# Adafruit_NeoKey_FeatherWing.net
KiCad netlist of a schematic drawn in EAGLE
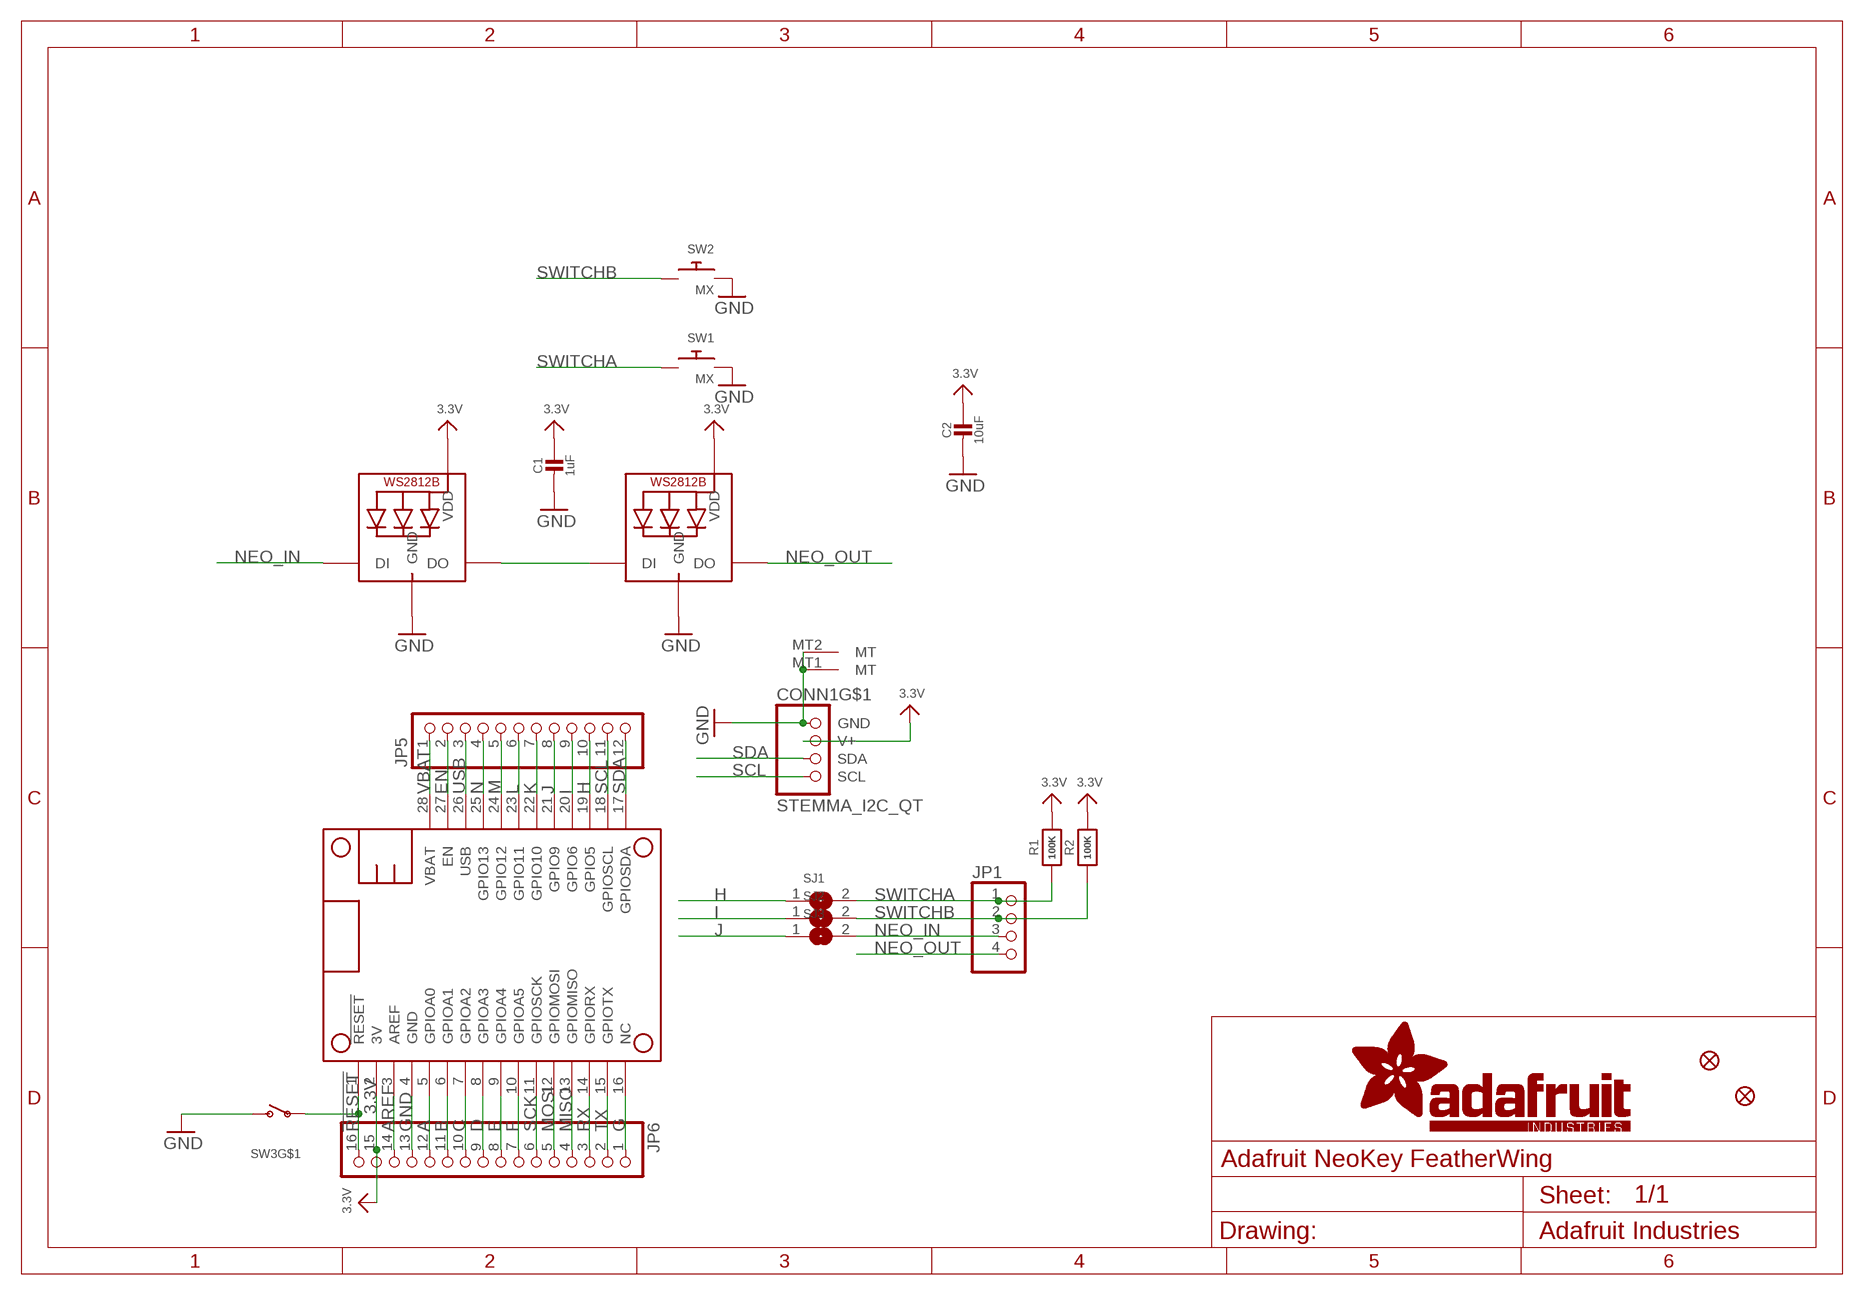
[diagram p0: schematic, sheet 1]

(export (version "E")
  (design (tool "Eeschema 10.0.6"))
  (components
    (comp (ref "C1")
      (value "1uF")
      (footprint "eagle-import:0603-NO")
      (libsource (lib "eagle-import") (part "CAP_CERAMIC0603_NO"))
    )
    (comp (ref "C2")
      (value "10uF")
      (footprint "eagle-import:0805-NO")
      (libsource (lib "eagle-import") (part "CAP_CERAMIC0805-NOOUTLINE"))
    )
    (comp (ref "CONN1")
      (value "STEMMA_I2C_QT")
      (footprint "eagle-import:JST_SH4")
      (libsource (lib "eagle-import") (part "STEMMA_I2C_QT"))
    )
    (comp (ref "FID1")
      (value "FIDUCIAL_1MM")
      (footprint "eagle-import:FIDUCIAL_1MM")
      (libsource (lib "eagle-import") (part "FIDUCIAL_1MM"))
    )
    (comp (ref "FID2")
      (value "FIDUCIAL_1MM")
      (footprint "eagle-import:FIDUCIAL_1MM")
      (libsource (lib "eagle-import") (part "FIDUCIAL_1MM"))
    )
    (comp (ref "JP1")
      (value "HEADER-1X4ROUND")
      (footprint "eagle-import:1X04_ROUND")
      (libsource (lib "eagle-import") (part "HEADER-1X4ROUND"))
    )
    (comp (ref "JP5")
      (value "HEADER-1X12")
      (footprint "eagle-import:1X12_ROUND")
      (libsource (lib "eagle-import") (part "HEADER-1X12"))
    )
    (comp (ref "JP6")
      (value "HEADER-1X16ROUND")
      (footprint "eagle-import:1X16_ROUND")
      (libsource (lib "eagle-import") (part "HEADER-1X16ROUND"))
    )
    (comp (ref "LED1")
      (value "WS2812B_SK6812E")
      (footprint "eagle-import:NEO3535_REVERSE")
      (libsource (lib "eagle-import") (part "WS2812B_SK6812E"))
    )
    (comp (ref "LED2")
      (value "WS2812B_SK6812E")
      (footprint "eagle-import:NEO3535_REVERSE")
      (libsource (lib "eagle-import") (part "WS2812B_SK6812E"))
    )
    (comp (ref "MS1")
      (value "FEATHERWING_NODIM")
      (footprint "eagle-import:FEATHERWING_NODIM")
      (libsource (lib "eagle-import") (part "FEATHERWING_NODIM"))
    )
    (comp (ref "R1")
      (value "100K")
      (footprint "eagle-import:0603-NO")
      (libsource (lib "eagle-import") (part "RESISTOR_0603_NOOUT"))
    )
    (comp (ref "R2")
      (value "100K")
      (footprint "eagle-import:0603-NO")
      (libsource (lib "eagle-import") (part "RESISTOR_0603_NOOUT"))
    )
    (comp (ref "SJ1")
      (value "SOLDERJUMPERCLOSED")
      (footprint "eagle-import:SOLDERJUMPER_CLOSEDWIRE")
      (libsource (lib "eagle-import") (part "SOLDERJUMPERCLOSED"))
    )
    (comp (ref "SJ2")
      (value "SOLDERJUMPERCLOSED")
      (footprint "eagle-import:SOLDERJUMPER_CLOSEDWIRE")
      (libsource (lib "eagle-import") (part "SOLDERJUMPERCLOSED"))
    )
    (comp (ref "SJ3")
      (value "SOLDERJUMPERCLOSED")
      (footprint "eagle-import:SOLDERJUMPER_CLOSEDWIRE")
      (libsource (lib "eagle-import") (part "SOLDERJUMPERCLOSED"))
    )
    (comp (ref "SW1")
      (value "MX")
      (footprint "eagle-import:KAILH_SOCKET")
      (libsource (lib "eagle-import") (part "SWITCH_PUSHBUTTON_KAILH_SOCKET"))
    )
    (comp (ref "SW2")
      (value "MX")
      (footprint "eagle-import:KAILH_SOCKET")
      (libsource (lib "eagle-import") (part "SWITCH_PUSHBUTTON_KAILH_SOCKET"))
    )
    (comp (ref "SW3")
      (value "SWITCH_SPST_TACT_RA")
      (footprint "eagle-import:SPST_TACTILE_RA")
      (libsource (lib "eagle-import") (part "SWITCH_SPST_TACT_RA"))
    )
  )
  (nets
    (net (code "1") (name "/A") (class "Default")
      (node (ref "JP6") (pin "12") (pinfunction "12_12") (pintype "passive"))
      (node (ref "MS1") (pin "5") (pinfunction "GPIOA0_5") (pintype "bidirectional"))
    )
    (net (code "2") (name "/AREF") (class "Default")
      (node (ref "JP6") (pin "14") (pinfunction "14_14") (pintype "passive"))
      (node (ref "MS1") (pin "3") (pinfunction "AREF_3") (pintype "passive"))
    )
    (net (code "3") (name "/B") (class "Default")
      (node (ref "JP6") (pin "11") (pinfunction "11_11") (pintype "passive"))
      (node (ref "MS1") (pin "6") (pinfunction "GPIOA1_6") (pintype "bidirectional"))
    )
    (net (code "4") (name "/C") (class "Default")
      (node (ref "JP6") (pin "10") (pinfunction "10_10") (pintype "passive"))
      (node (ref "MS1") (pin "7") (pinfunction "GPIOA2_7") (pintype "bidirectional"))
    )
    (net (code "5") (name "/D") (class "Default")
      (node (ref "JP6") (pin "9") (pinfunction "9_9") (pintype "passive"))
      (node (ref "MS1") (pin "8") (pinfunction "GPIOA3_8") (pintype "bidirectional"))
    )
    (net (code "6") (name "/E") (class "Default")
      (node (ref "JP6") (pin "8") (pinfunction "8_8") (pintype "passive"))
      (node (ref "MS1") (pin "9") (pinfunction "GPIOA4_9") (pintype "bidirectional"))
    )
    (net (code "7") (name "/EN") (class "Default")
      (node (ref "JP5") (pin "2") (pinfunction "2_2") (pintype "passive"))
      (node (ref "MS1") (pin "27") (pinfunction "EN_27") (pintype "passive"))
    )
    (net (code "8") (name "/F") (class "Default")
      (node (ref "JP6") (pin "7") (pinfunction "7_7") (pintype "passive"))
      (node (ref "MS1") (pin "10") (pinfunction "GPIOA5_10") (pintype "bidirectional"))
    )
    (net (code "9") (name "/G") (class "Default")
      (node (ref "JP6") (pin "1") (pinfunction "1_1") (pintype "passive"))
      (node (ref "MS1") (pin "16") (pinfunction "NC_16") (pintype "passive"))
    )
    (net (code "10") (name "/H") (class "Default")
      (node (ref "JP5") (pin "10") (pinfunction "10_10") (pintype "passive"))
      (node (ref "MS1") (pin "19") (pinfunction "GPIO5_19") (pintype "bidirectional"))
      (node (ref "SJ1") (pin "1") (pinfunction "1_1") (pintype "passive"))
    )
    (net (code "11") (name "/I") (class "Default")
      (node (ref "JP5") (pin "9") (pinfunction "9_9") (pintype "passive"))
      (node (ref "MS1") (pin "20") (pinfunction "GPIO6_20") (pintype "bidirectional"))
      (node (ref "SJ2") (pin "1") (pinfunction "1_1") (pintype "passive"))
    )
    (net (code "12") (name "/J") (class "Default")
      (node (ref "JP5") (pin "8") (pinfunction "8_8") (pintype "passive"))
      (node (ref "MS1") (pin "21") (pinfunction "GPIO9_21") (pintype "bidirectional"))
      (node (ref "SJ3") (pin "1") (pinfunction "1_1") (pintype "passive"))
    )
    (net (code "13") (name "/K") (class "Default")
      (node (ref "JP5") (pin "7") (pinfunction "7_7") (pintype "passive"))
      (node (ref "MS1") (pin "22") (pinfunction "GPIO10_22") (pintype "bidirectional"))
    )
    (net (code "14") (name "/L") (class "Default")
      (node (ref "JP5") (pin "6") (pinfunction "6_6") (pintype "passive"))
      (node (ref "MS1") (pin "23") (pinfunction "GPIO11_23") (pintype "bidirectional"))
    )
    (net (code "15") (name "/M") (class "Default")
      (node (ref "JP5") (pin "5") (pinfunction "5_5") (pintype "passive"))
      (node (ref "MS1") (pin "24") (pinfunction "GPIO12_24") (pintype "bidirectional"))
    )
    (net (code "16") (name "/MISO") (class "Default")
      (node (ref "JP6") (pin "4") (pinfunction "4_4") (pintype "passive"))
      (node (ref "MS1") (pin "13") (pinfunction "GPIOMISO_13") (pintype "bidirectional"))
    )
    (net (code "17") (name "/MOSI") (class "Default")
      (node (ref "JP6") (pin "5") (pinfunction "5_5") (pintype "passive"))
      (node (ref "MS1") (pin "12") (pinfunction "GPIOMOSI_12") (pintype "bidirectional"))
    )
    (net (code "18") (name "/N") (class "Default")
      (node (ref "JP5") (pin "4") (pinfunction "4_4") (pintype "passive"))
      (node (ref "MS1") (pin "25") (pinfunction "GPIO13_25") (pintype "bidirectional"))
    )
    (net (code "19") (name "/NEO_IN") (class "Default")
      (node (ref "JP1") (pin "3") (pinfunction "3_3") (pintype "passive"))
      (node (ref "LED2") (pin "4-DIN") (pinfunction "DI_4-DIN") (pintype "input"))
      (node (ref "SJ3") (pin "2") (pinfunction "2_2") (pintype "passive"))
    )
    (net (code "20") (name "/NEO_OUT") (class "Default")
      (node (ref "JP1") (pin "4") (pinfunction "4_4") (pintype "passive"))
      (node (ref "LED1") (pin "2-DOUT") (pinfunction "DO_2-DOUT") (pintype "output"))
    )
    (net (code "21") (name "/RX") (class "Default")
      (node (ref "JP6") (pin "3") (pinfunction "3_3") (pintype "passive"))
      (node (ref "MS1") (pin "14") (pinfunction "GPIORX_14") (pintype "bidirectional"))
    )
    (net (code "22") (name "/SCK") (class "Default")
      (node (ref "JP6") (pin "6") (pinfunction "6_6") (pintype "passive"))
      (node (ref "MS1") (pin "11") (pinfunction "GPIOSCK_11") (pintype "bidirectional"))
    )
    (net (code "23") (name "/SCL") (class "Default")
      (node (ref "CONN1") (pin "4") (pinfunction "SCL_4") (pintype "passive"))
      (node (ref "JP5") (pin "11") (pinfunction "11_11") (pintype "passive"))
      (node (ref "MS1") (pin "18") (pinfunction "GPIOSCL_18") (pintype "bidirectional"))
    )
    (net (code "24") (name "/SDA") (class "Default")
      (node (ref "CONN1") (pin "3") (pinfunction "SDA_3") (pintype "passive"))
      (node (ref "JP5") (pin "12") (pinfunction "12_12") (pintype "passive"))
      (node (ref "MS1") (pin "17") (pinfunction "GPIOSDA_17") (pintype "bidirectional"))
    )
    (net (code "25") (name "/SWITCHA") (class "Default")
      (node (ref "JP1") (pin "1") (pinfunction "1_1") (pintype "passive"))
      (node (ref "R1") (pin "1") (pinfunction "1_1") (pintype "passive"))
      (node (ref "SJ1") (pin "2") (pinfunction "2_2") (pintype "passive"))
      (node (ref "SW1") (pin "2") (pinfunction "P$2_2") (pintype "passive"))
    )
    (net (code "26") (name "/SWITCHB") (class "Default")
      (node (ref "JP1") (pin "2") (pinfunction "2_2") (pintype "passive"))
      (node (ref "R2") (pin "1") (pinfunction "1_1") (pintype "passive"))
      (node (ref "SJ2") (pin "2") (pinfunction "2_2") (pintype "passive"))
      (node (ref "SW2") (pin "2") (pinfunction "P$2_2") (pintype "passive"))
    )
    (net (code "27") (name "/TX") (class "Default")
      (node (ref "JP6") (pin "2") (pinfunction "2_2") (pintype "passive"))
      (node (ref "MS1") (pin "15") (pinfunction "GPIOTX_15") (pintype "bidirectional"))
    )
    (net (code "28") (name "/USB") (class "Default")
      (node (ref "JP5") (pin "3") (pinfunction "3_3") (pintype "passive"))
      (node (ref "MS1") (pin "26") (pinfunction "USB_26") (pintype "power_in"))
    )
    (net (code "29") (name "/VBAT") (class "Default")
      (node (ref "JP5") (pin "1") (pinfunction "1_1") (pintype "passive"))
      (node (ref "MS1") (pin "28") (pinfunction "VBAT_28") (pintype "power_in"))
    )
    (net (code "30") (name "/~{RESET}") (class "Default")
      (node (ref "JP6") (pin "16") (pinfunction "16_16") (pintype "passive"))
      (node (ref "MS1") (pin "1") (pinfunction "~{RESET}_1") (pintype "input"))
      (node (ref "SW3") (pin "1") (pinfunction "P_1") (pintype "passive"))
    )
    (net (code "31") (name "3.3V") (class "Default")
      (node (ref "C1") (pin "1") (pinfunction "1_1") (pintype "passive"))
      (node (ref "C2") (pin "1") (pinfunction "1_1") (pintype "passive"))
      (node (ref "CONN1") (pin "2") (pinfunction "V+_2") (pintype "passive"))
      (node (ref "JP6") (pin "15") (pinfunction "15_15") (pintype "passive"))
      (node (ref "LED1") (pin "1-VDD") (pinfunction "VDD_1-VDD") (pintype "power_in"))
      (node (ref "LED2") (pin "1-VDD") (pinfunction "VDD_1-VDD") (pintype "power_in"))
      (node (ref "MS1") (pin "2") (pinfunction "3V_2") (pintype "power_in"))
      (node (ref "R1") (pin "2") (pinfunction "2_2") (pintype "passive"))
      (node (ref "R2") (pin "2") (pinfunction "2_2") (pintype "passive"))
    )
    (net (code "32") (name "GND") (class "Default")
      (node (ref "C1") (pin "2") (pinfunction "2_2") (pintype "passive"))
      (node (ref "C2") (pin "2") (pinfunction "2_2") (pintype "passive"))
      (node (ref "CONN1") (pin "1") (pinfunction "GND_1") (pintype "passive"))
      (node (ref "CONN1") (pin "MT1") (pinfunction "MT_MT1") (pintype "bidirectional"))
      (node (ref "CONN1") (pin "MT2") (pinfunction "MT_MT2") (pintype "bidirectional"))
      (node (ref "JP6") (pin "13") (pinfunction "13_13") (pintype "passive"))
      (node (ref "LED1") (pin "3-GND") (pinfunction "GND_3-GND") (pintype "power_in"))
      (node (ref "LED2") (pin "3-GND") (pinfunction "GND_3-GND") (pintype "power_in"))
      (node (ref "MS1") (pin "4") (pinfunction "GND_4") (pintype "power_in"))
      (node (ref "SW1") (pin "1") (pinfunction "P$1_1") (pintype "passive"))
      (node (ref "SW2") (pin "1") (pinfunction "P$1_1") (pintype "passive"))
      (node (ref "SW3") (pin "2") (pinfunction "S_2") (pintype "passive"))
    )
    (net (code "33") (name "Net-(LED1-DI)") (class "Default")
      (node (ref "LED1") (pin "4-DIN") (pinfunction "DI_4-DIN") (pintype "input"))
      (node (ref "LED2") (pin "2-DOUT") (pinfunction "DO_2-DOUT") (pintype "output"))
    )
  )
)
